# LVDS_Splitter.net
KiCad netlist of a schematic drawn in Altium Designer
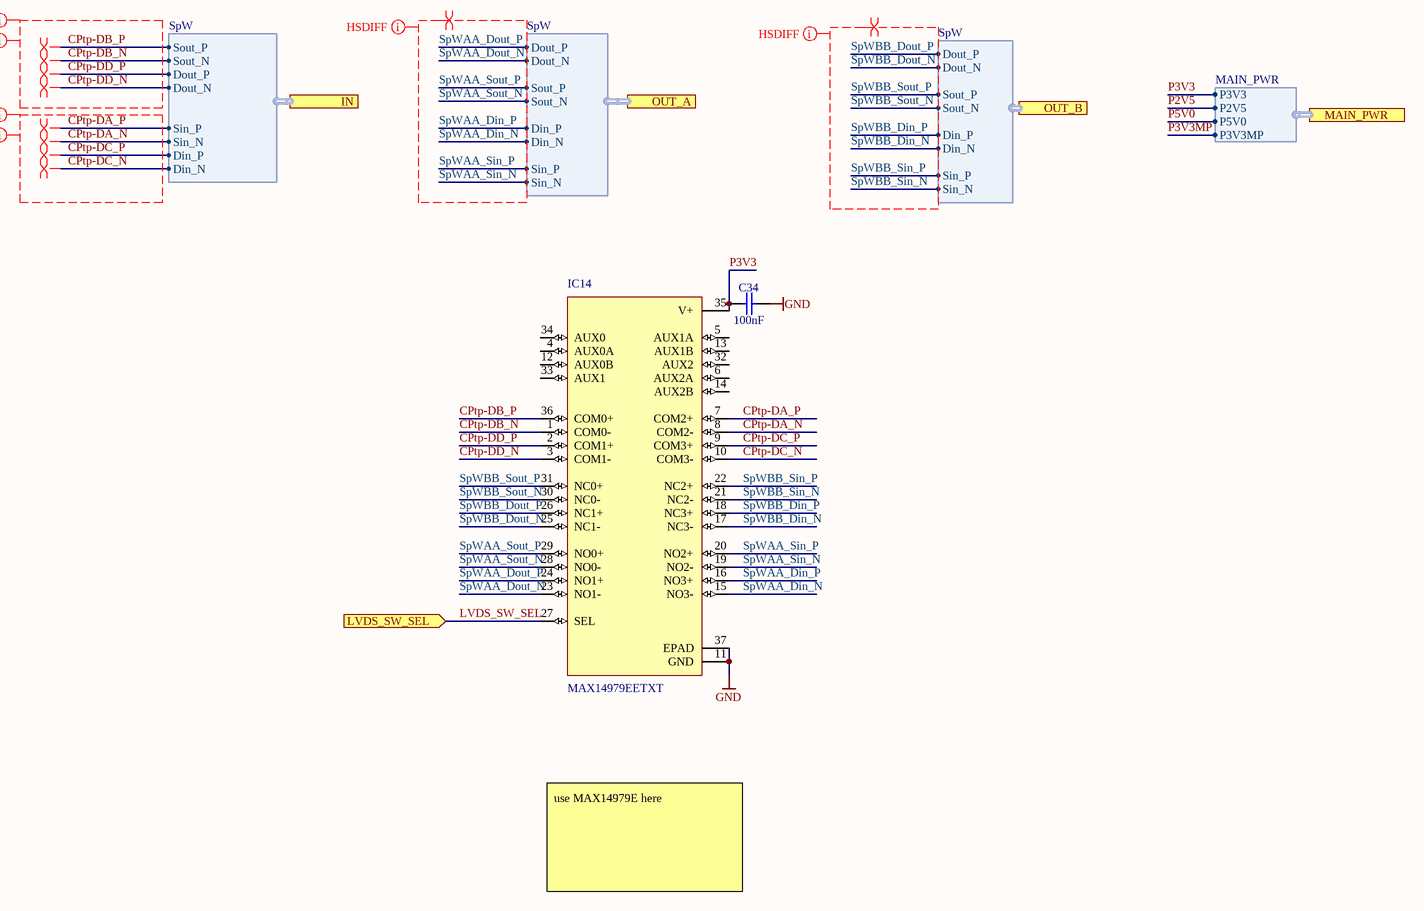
[diagram p0: LVDS_Splitter.SchDoc]

(export (version "E")
  (design (tool "Eeschema 10.0.6"))
  (components
    (comp (ref "C34")
      (value "100nF")
      (footprint "CAPC0603X33N")
      (description "Non-polarised capacitor")
      (fields
        (field (name "TOLERANCE") "±10%")
        (field (name "VOLTAGE") "6.3V")
        (field (name "AUTHOR") "CERN DEM JLC")
      )
      (libsource (lib "Capacitors") (part "Capacitor - non polarized"))
    )
    (comp (ref "IC14")
      (value "MAX14979EETXT")
      (footprint "QFN50P600X600X90-37N-S425")
      (description "IC SWITCH HIGH BW LVDS 36TQFN")
      (fields (field (name "MF") "Maxim Integrated") (field (name "MP") "MAX14979EETX+"))
      (libsource (lib "MAX14979EETXT") (part "MAX14979EETXT"))
    )
  )
  (nets
    (net (code "3") (name "/CPtp-DA_N") (class "Default")
      (node (ref "IC14") (pin "8") (pinfunction "COM2-_8") (pintype "bidirectional"))
    )
    (net (code "4") (name "/CPtp-DA_P") (class "Default")
      (node (ref "IC14") (pin "7") (pinfunction "COM2+_7") (pintype "bidirectional"))
    )
    (net (code "5") (name "/CPtp-DB_N") (class "Default")
      (node (ref "IC14") (pin "1") (pinfunction "COM0-_1") (pintype "bidirectional"))
    )
    (net (code "6") (name "/CPtp-DB_P") (class "Default")
      (node (ref "IC14") (pin "36") (pinfunction "COM0+_36") (pintype "bidirectional"))
    )
    (net (code "7") (name "/CPtp-DC_N") (class "Default")
      (node (ref "IC14") (pin "10") (pinfunction "COM3-_10") (pintype "bidirectional"))
    )
    (net (code "8") (name "/CPtp-DC_P") (class "Default")
      (node (ref "IC14") (pin "9") (pinfunction "COM3+_9") (pintype "bidirectional"))
    )
    (net (code "9") (name "/CPtp-DD_N") (class "Default")
      (node (ref "IC14") (pin "3") (pinfunction "COM1-_3") (pintype "bidirectional"))
    )
    (net (code "10") (name "/CPtp-DD_P") (class "Default")
      (node (ref "IC14") (pin "2") (pinfunction "COM1+_2") (pintype "bidirectional"))
    )
    (net (code "11") (name "/LVDS_SW_SEL") (class "Default")
      (node (ref "IC14") (pin "27") (pinfunction "SEL_27") (pintype "bidirectional"))
    )
    (net (code "13") (name "/P3V3") (class "Default")
      (node (ref "C34") (pin "1") (pinfunction "1_1") (pintype "passive"))
      (node (ref "IC14") (pin "35") (pinfunction "V+_35") (pintype "power_in"))
    )
    (net (code "16") (name "/SpWAA_Din_N") (class "Default")
      (node (ref "IC14") (pin "15") (pinfunction "NO3-_15") (pintype "bidirectional"))
    )
    (net (code "17") (name "/SpWAA_Din_P") (class "Default")
      (node (ref "IC14") (pin "16") (pinfunction "NO3+_16") (pintype "bidirectional"))
    )
    (net (code "18") (name "/SpWAA_Dout_N") (class "Default")
      (node (ref "IC14") (pin "23") (pinfunction "NO1-_23") (pintype "bidirectional"))
    )
    (net (code "19") (name "/SpWAA_Dout_P") (class "Default")
      (node (ref "IC14") (pin "24") (pinfunction "NO1+_24") (pintype "bidirectional"))
    )
    (net (code "20") (name "/SpWAA_Sin_N") (class "Default")
      (node (ref "IC14") (pin "19") (pinfunction "NO2-_19") (pintype "bidirectional"))
    )
    (net (code "21") (name "/SpWAA_Sin_P") (class "Default")
      (node (ref "IC14") (pin "20") (pinfunction "NO2+_20") (pintype "bidirectional"))
    )
    (net (code "22") (name "/SpWAA_Sout_N") (class "Default")
      (node (ref "IC14") (pin "28") (pinfunction "NO0-_28") (pintype "bidirectional"))
    )
    (net (code "23") (name "/SpWAA_Sout_P") (class "Default")
      (node (ref "IC14") (pin "29") (pinfunction "NO0+_29") (pintype "bidirectional"))
    )
    (net (code "24") (name "/SpWBB_Din_N") (class "Default")
      (node (ref "IC14") (pin "17") (pinfunction "NC3-_17") (pintype "bidirectional"))
    )
    (net (code "25") (name "/SpWBB_Din_P") (class "Default")
      (node (ref "IC14") (pin "18") (pinfunction "NC3+_18") (pintype "bidirectional"))
    )
    (net (code "26") (name "/SpWBB_Dout_N") (class "Default")
      (node (ref "IC14") (pin "25") (pinfunction "NC1-_25") (pintype "bidirectional"))
    )
    (net (code "27") (name "/SpWBB_Dout_P") (class "Default")
      (node (ref "IC14") (pin "26") (pinfunction "NC1+_26") (pintype "bidirectional"))
    )
    (net (code "28") (name "/SpWBB_Sin_N") (class "Default")
      (node (ref "IC14") (pin "21") (pinfunction "NC2-_21") (pintype "bidirectional"))
    )
    (net (code "29") (name "/SpWBB_Sin_P") (class "Default")
      (node (ref "IC14") (pin "22") (pinfunction "NC2+_22") (pintype "bidirectional"))
    )
    (net (code "30") (name "/SpWBB_Sout_N") (class "Default")
      (node (ref "IC14") (pin "30") (pinfunction "NC0-_30") (pintype "bidirectional"))
    )
    (net (code "31") (name "/SpWBB_Sout_P") (class "Default")
      (node (ref "IC14") (pin "31") (pinfunction "NC0+_31") (pintype "bidirectional"))
    )
    (net (code "34") (name "GND") (class "Default")
      (node (ref "C34") (pin "2") (pinfunction "2_2") (pintype "passive"))
      (node (ref "IC14") (pin "11") (pinfunction "GND_11") (pintype "power_in"))
      (node (ref "IC14") (pin "37") (pinfunction "EPAD_37") (pintype "power_in"))
    )
    (net (code "35") (name "unconnected-(IC14-AUX0-Pad34)") (class "Default")
      (node (ref "IC14") (pin "34") (pinfunction "AUX0_34") (pintype "bidirectional"))
    )
    (net (code "36") (name "unconnected-(IC14-AUX0A-Pad4)") (class "Default")
      (node (ref "IC14") (pin "4") (pinfunction "AUX0A_4") (pintype "bidirectional"))
    )
    (net (code "37") (name "unconnected-(IC14-AUX0B-Pad12)") (class "Default")
      (node (ref "IC14") (pin "12") (pinfunction "AUX0B_12") (pintype "bidirectional"))
    )
    (net (code "38") (name "unconnected-(IC14-AUX1-Pad33)") (class "Default")
      (node (ref "IC14") (pin "33") (pinfunction "AUX1_33") (pintype "bidirectional"))
    )
    (net (code "39") (name "unconnected-(IC14-AUX1A-Pad5)") (class "Default")
      (node (ref "IC14") (pin "5") (pinfunction "AUX1A_5") (pintype "bidirectional"))
    )
    (net (code "40") (name "unconnected-(IC14-AUX1B-Pad13)") (class "Default")
      (node (ref "IC14") (pin "13") (pinfunction "AUX1B_13") (pintype "bidirectional"))
    )
    (net (code "41") (name "unconnected-(IC14-AUX2-Pad32)") (class "Default")
      (node (ref "IC14") (pin "32") (pinfunction "AUX2_32") (pintype "bidirectional"))
    )
    (net (code "42") (name "unconnected-(IC14-AUX2A-Pad6)") (class "Default")
      (node (ref "IC14") (pin "6") (pinfunction "AUX2A_6") (pintype "bidirectional"))
    )
    (net (code "43") (name "unconnected-(IC14-AUX2B-Pad14)") (class "Default")
      (node (ref "IC14") (pin "14") (pinfunction "AUX2B_14") (pintype "bidirectional"))
    )
  )
)
